# RedisignVaractorTline144Mhz.net
KiCad netlist of a schematic drawn in Altium Designer
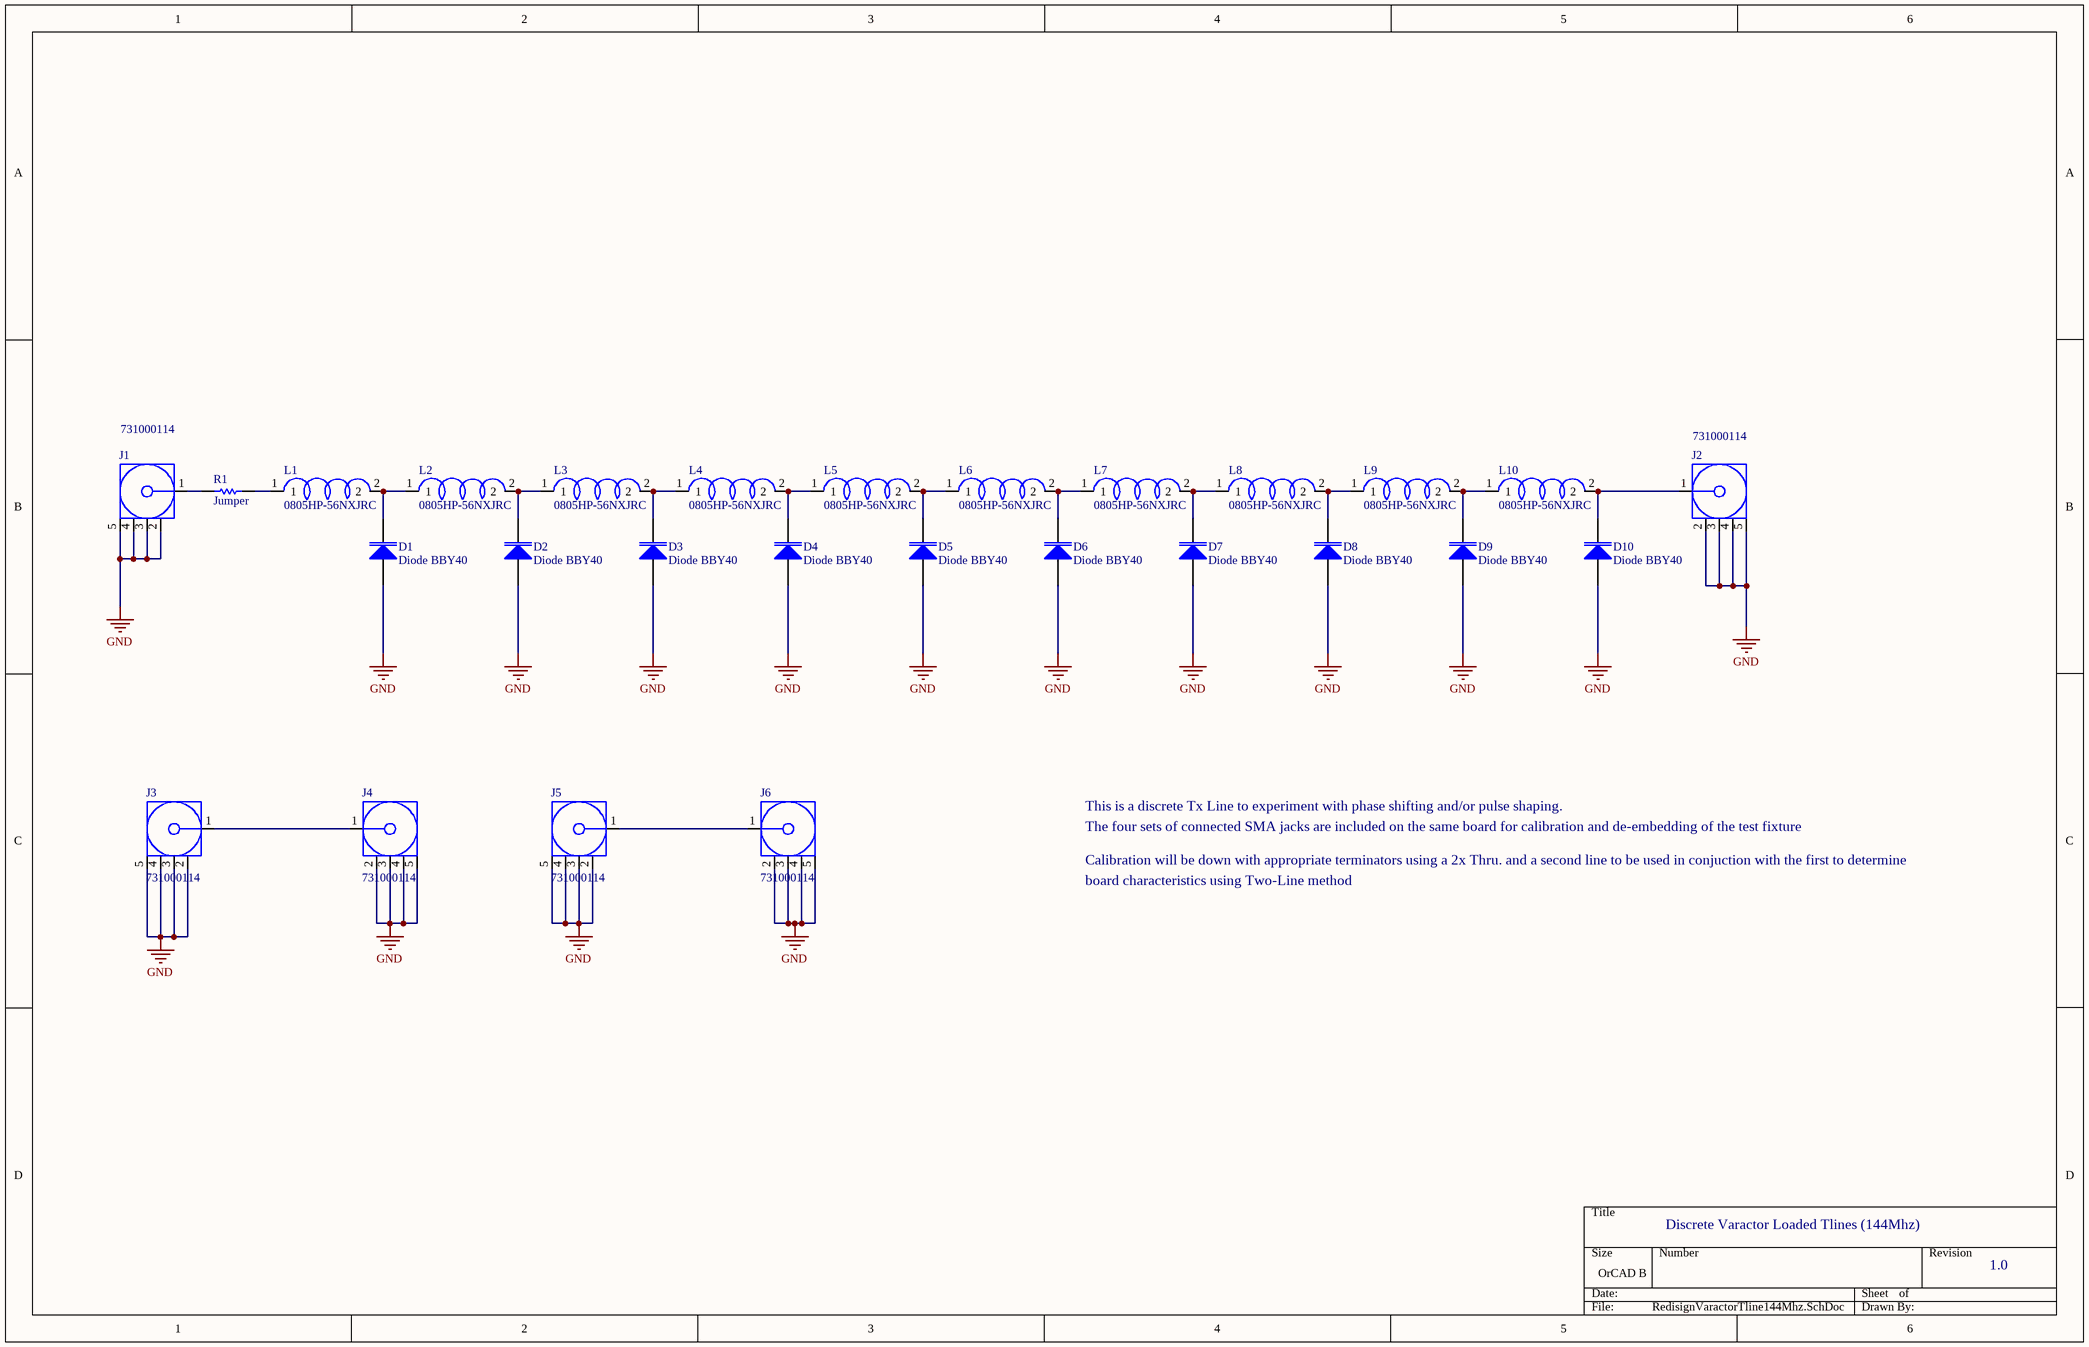
[diagram p0: RedisignVaractorTline144Mhz.SchDoc]

(export (version "E")
  (design (tool "Eeschema 10.0.6"))
  (components
    (comp (ref "D1")
      (value "Diode BBY40")
      (footprint "SOT23_N")
      (description "SOT23 Silicon Planar Variable Capacitance Diode")
      (fields (field (name "PUBLISHER") "Altium Limited"))
      (libsource (lib "Miscellaneous Devices") (part "Diode BBY40"))
    )
    (comp (ref "D2")
      (value "Diode BBY40")
      (footprint "SOT23_N")
      (description "SOT23 Silicon Planar Variable Capacitance Diode")
      (fields (field (name "PUBLISHER") "Altium Limited"))
      (libsource (lib "Miscellaneous Devices") (part "Diode BBY40"))
    )
    (comp (ref "D3")
      (value "Diode BBY40")
      (footprint "SOT23_N")
      (description "SOT23 Silicon Planar Variable Capacitance Diode")
      (fields (field (name "PUBLISHER") "Altium Limited"))
      (libsource (lib "Miscellaneous Devices") (part "Diode BBY40"))
    )
    (comp (ref "D4")
      (value "Diode BBY40")
      (footprint "SOT23_N")
      (description "SOT23 Silicon Planar Variable Capacitance Diode")
      (fields (field (name "PUBLISHER") "Altium Limited"))
      (libsource (lib "Miscellaneous Devices") (part "Diode BBY40"))
    )
    (comp (ref "D5")
      (value "Diode BBY40")
      (footprint "SOT23_N")
      (description "SOT23 Silicon Planar Variable Capacitance Diode")
      (fields (field (name "PUBLISHER") "Altium Limited"))
      (libsource (lib "Miscellaneous Devices") (part "Diode BBY40"))
    )
    (comp (ref "D6")
      (value "Diode BBY40")
      (footprint "SOT23_N")
      (description "SOT23 Silicon Planar Variable Capacitance Diode")
      (fields (field (name "PUBLISHER") "Altium Limited"))
      (libsource (lib "Miscellaneous Devices") (part "Diode BBY40"))
    )
    (comp (ref "D7")
      (value "Diode BBY40")
      (footprint "SOT23_N")
      (description "SOT23 Silicon Planar Variable Capacitance Diode")
      (fields (field (name "PUBLISHER") "Altium Limited"))
      (libsource (lib "Miscellaneous Devices") (part "Diode BBY40"))
    )
    (comp (ref "D8")
      (value "Diode BBY40")
      (footprint "SOT23_N")
      (description "SOT23 Silicon Planar Variable Capacitance Diode")
      (fields (field (name "PUBLISHER") "Altium Limited"))
      (libsource (lib "Miscellaneous Devices") (part "Diode BBY40"))
    )
    (comp (ref "D9")
      (value "Diode BBY40")
      (footprint "SOT23_N")
      (description "SOT23 Silicon Planar Variable Capacitance Diode")
      (fields (field (name "PUBLISHER") "Altium Limited"))
      (libsource (lib "Miscellaneous Devices") (part "Diode BBY40"))
    )
    (comp (ref "D10")
      (value "Diode BBY40")
      (footprint "SOT23_N")
      (description "SOT23 Silicon Planar Variable Capacitance Diode")
      (fields (field (name "PUBLISHER") "Altium Limited"))
      (libsource (lib "Miscellaneous Devices") (part "Diode BBY40"))
    )
    (comp (ref "J1")
      (value "731000114")
      (footprint "MOLX-731000114_V")
      (description "SMA Right-Angle PCB Jack Receptacle, Brass Body, Gold Plated, 50 Ohm, 5-Pin THD, RoHS, Tray")
      (fields (field (name "MANUFACTURER") "Molex"))
      (libsource (lib "Altium Content Vault") (part "CN-S-4F-RF5"))
    )
    (comp (ref "J2")
      (value "731000114")
      (footprint "MOLX-731000114_V")
      (description "SMA Right-Angle PCB Jack Receptacle, Brass Body, Gold Plated, 50 Ohm, 5-Pin THD, RoHS, Tray")
      (fields (field (name "MANUFACTURER") "Molex"))
      (libsource (lib "Altium Content Vault") (part "CN-S-4F-RF5"))
    )
    (comp (ref "J3")
      (value "731000114")
      (footprint "MOLX-731000114_V")
      (description "SMA Right-Angle PCB Jack Receptacle, Brass Body, Gold Plated, 50 Ohm, 5-Pin THD, RoHS, Tray")
      (fields (field (name "MANUFACTURER") "Molex"))
      (libsource (lib "Altium Content Vault") (part "CN-S-4F-RF5"))
    )
    (comp (ref "J4")
      (value "731000114")
      (footprint "MOLX-731000114_V")
      (description "SMA Right-Angle PCB Jack Receptacle, Brass Body, Gold Plated, 50 Ohm, 5-Pin THD, RoHS, Tray")
      (fields (field (name "MANUFACTURER") "Molex"))
      (libsource (lib "Altium Content Vault") (part "CN-S-4F-RF5"))
    )
    (comp (ref "J5")
      (value "731000114")
      (footprint "MOLX-731000114_V")
      (description "SMA Right-Angle PCB Jack Receptacle, Brass Body, Gold Plated, 50 Ohm, 5-Pin THD, RoHS, Tray")
      (fields (field (name "MANUFACTURER") "Molex"))
      (libsource (lib "Altium Content Vault") (part "CN-S-4F-RF5"))
    )
    (comp (ref "J6")
      (value "731000114")
      (footprint "MOLX-731000114_V")
      (description "SMA Right-Angle PCB Jack Receptacle, Brass Body, Gold Plated, 50 Ohm, 5-Pin THD, RoHS, Tray")
      (fields (field (name "MANUFACTURER") "Molex"))
      (libsource (lib "Altium Content Vault") (part "CN-S-4F-RF5"))
    )
    (comp (ref "L1")
      (value "0805HP-56NXJRC")
      (footprint "0805HQ SERIES")
      (description "0805HP-56NXJRC Coilcraft Variable Inductor")
      (fields (field (name "MANUFACTURER") "Coilcraft"))
      (libsource (lib "114MhzDiscreteTxline") (part "0805HP-56NXJRC"))
    )
    (comp (ref "L2")
      (value "0805HP-56NXJRC")
      (footprint "0805HQ SERIES")
      (description "0805HP-56NXJRC Coilcraft Variable Inductor")
      (fields (field (name "MANUFACTURER") "Coilcraft"))
      (libsource (lib "114MhzDiscreteTxline") (part "0805HP-56NXJRC"))
    )
    (comp (ref "L3")
      (value "0805HP-56NXJRC")
      (footprint "0805HQ SERIES")
      (description "0805HP-56NXJRC Coilcraft Variable Inductor")
      (fields (field (name "MANUFACTURER") "Coilcraft"))
      (libsource (lib "114MhzDiscreteTxline") (part "0805HP-56NXJRC"))
    )
    (comp (ref "L4")
      (value "0805HP-56NXJRC")
      (footprint "0805HQ SERIES")
      (description "0805HP-56NXJRC Coilcraft Variable Inductor")
      (fields (field (name "MANUFACTURER") "Coilcraft"))
      (libsource (lib "114MhzDiscreteTxline") (part "0805HP-56NXJRC"))
    )
    (comp (ref "L5")
      (value "0805HP-56NXJRC")
      (footprint "0805HQ SERIES")
      (description "0805HP-56NXJRC Coilcraft Variable Inductor")
      (fields (field (name "MANUFACTURER") "Coilcraft"))
      (libsource (lib "114MhzDiscreteTxline") (part "0805HP-56NXJRC"))
    )
    (comp (ref "L6")
      (value "0805HP-56NXJRC")
      (footprint "0805HQ SERIES")
      (description "0805HP-56NXJRC Coilcraft Variable Inductor")
      (fields (field (name "MANUFACTURER") "Coilcraft"))
      (libsource (lib "114MhzDiscreteTxline") (part "0805HP-56NXJRC"))
    )
    (comp (ref "L7")
      (value "0805HP-56NXJRC")
      (footprint "0805HQ SERIES")
      (description "0805HP-56NXJRC Coilcraft Variable Inductor")
      (fields (field (name "MANUFACTURER") "Coilcraft"))
      (libsource (lib "114MhzDiscreteTxline") (part "0805HP-56NXJRC"))
    )
    (comp (ref "L8")
      (value "0805HP-56NXJRC")
      (footprint "0805HQ SERIES")
      (description "0805HP-56NXJRC Coilcraft Variable Inductor")
      (fields (field (name "MANUFACTURER") "Coilcraft"))
      (libsource (lib "114MhzDiscreteTxline") (part "0805HP-56NXJRC"))
    )
    (comp (ref "L9")
      (value "0805HP-56NXJRC")
      (footprint "0805HQ SERIES")
      (description "0805HP-56NXJRC Coilcraft Variable Inductor")
      (fields (field (name "MANUFACTURER") "Coilcraft"))
      (libsource (lib "114MhzDiscreteTxline") (part "0805HP-56NXJRC"))
    )
    (comp (ref "L10")
      (value "0805HP-56NXJRC")
      (footprint "0805HQ SERIES")
      (description "0805HP-56NXJRC Coilcraft Variable Inductor")
      (fields (field (name "MANUFACTURER") "Coilcraft"))
      (libsource (lib "114MhzDiscreteTxline") (part "0805HP-56NXJRC"))
    )
    (comp (ref "R1")
      (value "Jumper")
      (footprint "RESC2013X70X40NL20T20")
      (description "Chip Resistor, 0 Ohm, +/- 1%, 0.125 W, -55 to 155 degC, 0805 (2012 Metric), RoHS, Tape and Reel")
      (fields (field (name "PARTNUMBER") "ERJ-6GEY0R00V") (field (name "TOLERANCE") "5%"))
      (libsource (lib "Altium Content Vault") (part "RES-2"))
    )
  )
  (nets
    (net (code "1") (name "GND") (class "Default")
      (node (ref "D1") (pin "3") (pinfunction "A_3") (pintype "passive"))
      (node (ref "D10") (pin "3") (pinfunction "A_3") (pintype "passive"))
      (node (ref "D2") (pin "3") (pinfunction "A_3") (pintype "passive"))
      (node (ref "D3") (pin "3") (pinfunction "A_3") (pintype "passive"))
      (node (ref "D4") (pin "3") (pinfunction "A_3") (pintype "passive"))
      (node (ref "D5") (pin "3") (pinfunction "A_3") (pintype "passive"))
      (node (ref "D6") (pin "3") (pinfunction "A_3") (pintype "passive"))
      (node (ref "D7") (pin "3") (pinfunction "A_3") (pintype "passive"))
      (node (ref "D8") (pin "3") (pinfunction "A_3") (pintype "passive"))
      (node (ref "D9") (pin "3") (pinfunction "A_3") (pintype "passive"))
      (node (ref "J1") (pin "2") (pinfunction "2_2") (pintype "passive"))
      (node (ref "J1") (pin "3") (pinfunction "3_3") (pintype "passive"))
      (node (ref "J1") (pin "4") (pinfunction "4_4") (pintype "passive"))
      (node (ref "J1") (pin "5") (pinfunction "5_5") (pintype "passive"))
      (node (ref "J2") (pin "2") (pinfunction "2_2") (pintype "passive"))
      (node (ref "J2") (pin "3") (pinfunction "3_3") (pintype "passive"))
      (node (ref "J2") (pin "4") (pinfunction "4_4") (pintype "passive"))
      (node (ref "J2") (pin "5") (pinfunction "5_5") (pintype "passive"))
      (node (ref "J3") (pin "2") (pinfunction "2_2") (pintype "passive"))
      (node (ref "J3") (pin "3") (pinfunction "3_3") (pintype "passive"))
      (node (ref "J3") (pin "4") (pinfunction "4_4") (pintype "passive"))
      (node (ref "J3") (pin "5") (pinfunction "5_5") (pintype "passive"))
      (node (ref "J4") (pin "2") (pinfunction "2_2") (pintype "passive"))
      (node (ref "J4") (pin "3") (pinfunction "3_3") (pintype "passive"))
      (node (ref "J4") (pin "4") (pinfunction "4_4") (pintype "passive"))
      (node (ref "J4") (pin "5") (pinfunction "5_5") (pintype "passive"))
      (node (ref "J5") (pin "2") (pinfunction "2_2") (pintype "passive"))
      (node (ref "J5") (pin "3") (pinfunction "3_3") (pintype "passive"))
      (node (ref "J5") (pin "4") (pinfunction "4_4") (pintype "passive"))
      (node (ref "J5") (pin "5") (pinfunction "5_5") (pintype "passive"))
      (node (ref "J6") (pin "2") (pinfunction "2_2") (pintype "passive"))
      (node (ref "J6") (pin "3") (pinfunction "3_3") (pintype "passive"))
      (node (ref "J6") (pin "4") (pinfunction "4_4") (pintype "passive"))
      (node (ref "J6") (pin "5") (pinfunction "5_5") (pintype "passive"))
    )
    (net (code "2") (name "Net-(D1-K)") (class "Default")
      (node (ref "D1") (pin "1") (pinfunction "K_1") (pintype "passive"))
      (node (ref "L1") (pin "2") (pinfunction "2_2") (pintype "passive"))
      (node (ref "L2") (pin "1") (pinfunction "1_1") (pintype "passive"))
    )
    (net (code "3") (name "Net-(D2-K)") (class "Default")
      (node (ref "D2") (pin "1") (pinfunction "K_1") (pintype "passive"))
      (node (ref "L2") (pin "2") (pinfunction "2_2") (pintype "passive"))
      (node (ref "L3") (pin "1") (pinfunction "1_1") (pintype "passive"))
    )
    (net (code "4") (name "Net-(D3-K)") (class "Default")
      (node (ref "D3") (pin "1") (pinfunction "K_1") (pintype "passive"))
      (node (ref "L3") (pin "2") (pinfunction "2_2") (pintype "passive"))
      (node (ref "L4") (pin "1") (pinfunction "1_1") (pintype "passive"))
    )
    (net (code "5") (name "Net-(D4-K)") (class "Default")
      (node (ref "D4") (pin "1") (pinfunction "K_1") (pintype "passive"))
      (node (ref "L4") (pin "2") (pinfunction "2_2") (pintype "passive"))
      (node (ref "L5") (pin "1") (pinfunction "1_1") (pintype "passive"))
    )
    (net (code "6") (name "Net-(D5-K)") (class "Default")
      (node (ref "D5") (pin "1") (pinfunction "K_1") (pintype "passive"))
      (node (ref "L5") (pin "2") (pinfunction "2_2") (pintype "passive"))
      (node (ref "L6") (pin "1") (pinfunction "1_1") (pintype "passive"))
    )
    (net (code "7") (name "Net-(D6-K)") (class "Default")
      (node (ref "D6") (pin "1") (pinfunction "K_1") (pintype "passive"))
      (node (ref "L6") (pin "2") (pinfunction "2_2") (pintype "passive"))
      (node (ref "L7") (pin "1") (pinfunction "1_1") (pintype "passive"))
    )
    (net (code "8") (name "Net-(D7-K)") (class "Default")
      (node (ref "D7") (pin "1") (pinfunction "K_1") (pintype "passive"))
      (node (ref "L7") (pin "2") (pinfunction "2_2") (pintype "passive"))
      (node (ref "L8") (pin "1") (pinfunction "1_1") (pintype "passive"))
    )
    (net (code "9") (name "Net-(D8-K)") (class "Default")
      (node (ref "D8") (pin "1") (pinfunction "K_1") (pintype "passive"))
      (node (ref "L8") (pin "2") (pinfunction "2_2") (pintype "passive"))
      (node (ref "L9") (pin "1") (pinfunction "1_1") (pintype "passive"))
    )
    (net (code "10") (name "Net-(D9-K)") (class "Default")
      (node (ref "D9") (pin "1") (pinfunction "K_1") (pintype "passive"))
      (node (ref "L10") (pin "1") (pinfunction "1_1") (pintype "passive"))
      (node (ref "L9") (pin "2") (pinfunction "2_2") (pintype "passive"))
    )
    (net (code "11") (name "Net-(D10-K)") (class "Default")
      (node (ref "D10") (pin "1") (pinfunction "K_1") (pintype "passive"))
      (node (ref "J2") (pin "1") (pinfunction "1_1") (pintype "passive"))
      (node (ref "L10") (pin "2") (pinfunction "2_2") (pintype "passive"))
    )
    (net (code "12") (name "Net-(J1-Pad1)") (class "Default")
      (node (ref "J1") (pin "1") (pinfunction "1_1") (pintype "passive"))
      (node (ref "R1") (pin "1") (pinfunction "1_1") (pintype "passive"))
    )
    (net (code "13") (name "Net-(J3-Pad1)") (class "Default")
      (node (ref "J3") (pin "1") (pinfunction "1_1") (pintype "passive"))
      (node (ref "J4") (pin "1") (pinfunction "1_1") (pintype "passive"))
    )
    (net (code "14") (name "Net-(J5-Pad1)") (class "Default")
      (node (ref "J5") (pin "1") (pinfunction "1_1") (pintype "passive"))
      (node (ref "J6") (pin "1") (pinfunction "1_1") (pintype "passive"))
    )
    (net (code "15") (name "Net-(L1-Pad1)") (class "Default")
      (node (ref "L1") (pin "1") (pinfunction "1_1") (pintype "passive"))
      (node (ref "R1") (pin "2") (pinfunction "2_2") (pintype "passive"))
    )
  )
)
